# mark3.net
KiCad netlist of a schematic drawn in Altium Designer
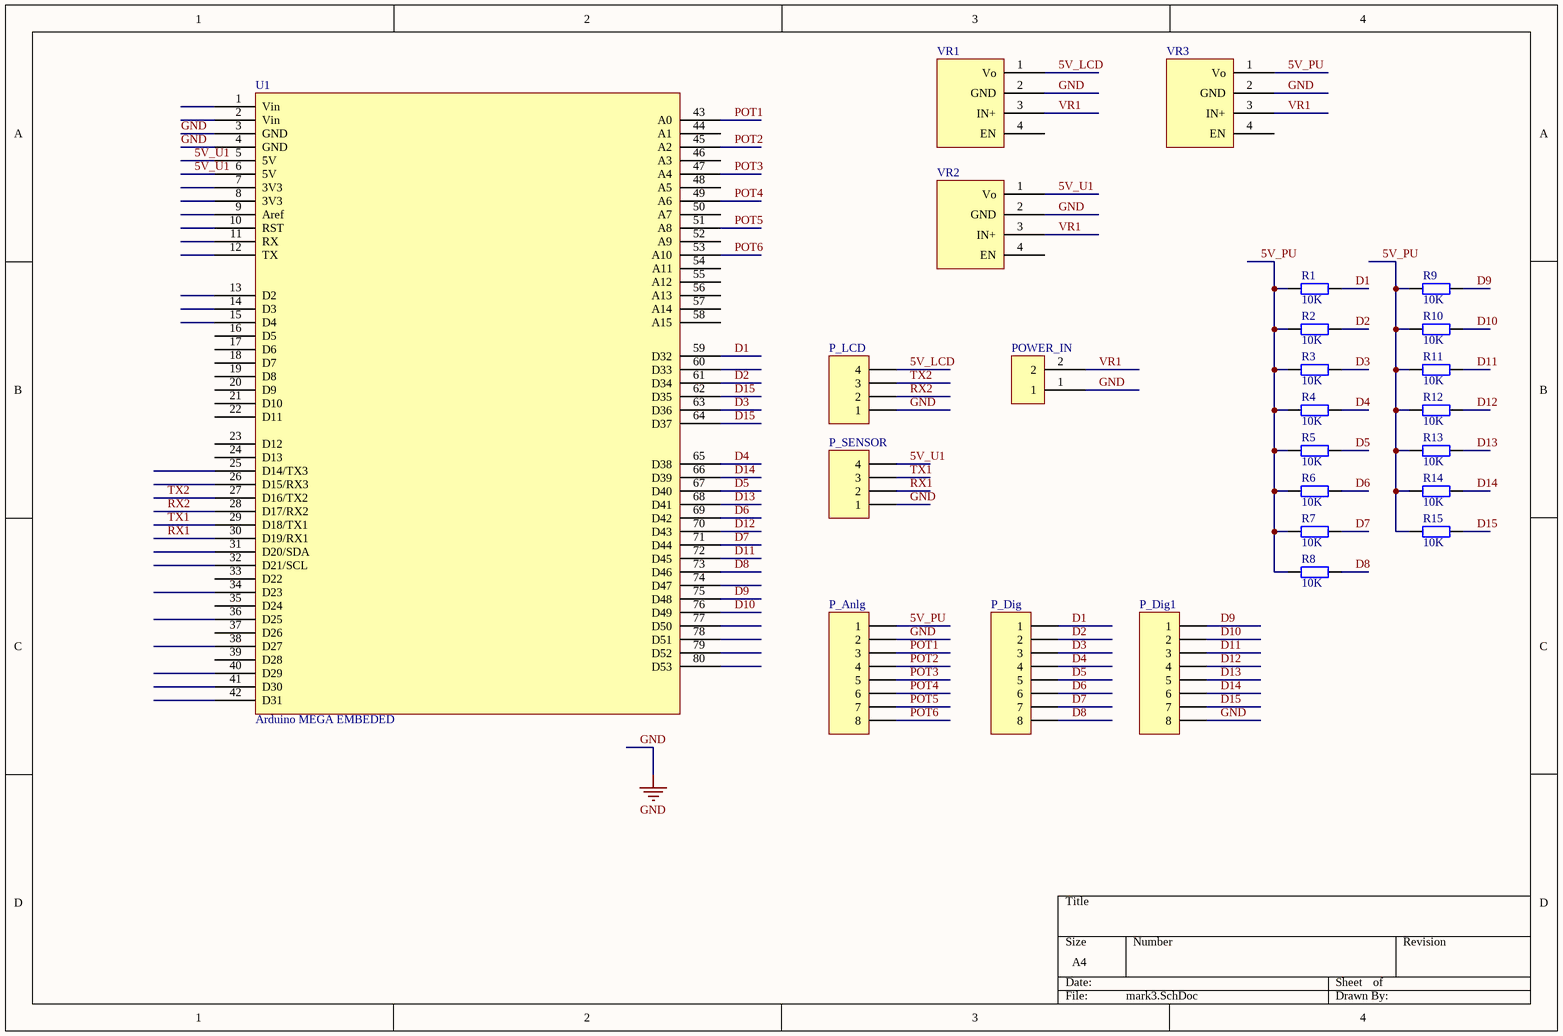
[diagram p0: mark3.SchDoc]

(export (version "E")
  (design (tool "Eeschema 10.0.6"))
  (components
    (comp (ref "POWER_IN")
      (value "Term_2Pin_Green")
      (footprint "TERM_2P_GREEN")
      (libsource (lib "arduino") (part "Term_2Pin_Blck"))
    )
    (comp (ref "P_Anlg")
      (value "Header 8")
      (footprint "TERM_8P_GREEN")
      (description "Header, 8-Pin")
      (fields (field (name "PUBLISHER") "Altium Limited"))
      (libsource (lib "Miscellaneous Connectors") (part "Header 8"))
    )
    (comp (ref "P_Dig")
      (value "Header 8")
      (footprint "TERM_8P_GREEN")
      (description "Header, 8-Pin")
      (fields (field (name "PUBLISHER") "Altium Limited"))
      (libsource (lib "Miscellaneous Connectors") (part "Header 8"))
    )
    (comp (ref "P_Dig1")
      (value "Header 8")
      (footprint "TERM_8P_GREEN")
      (description "Header, 8-Pin")
      (fields (field (name "PUBLISHER") "Altium Limited"))
      (libsource (lib "Miscellaneous Connectors") (part "Header 8"))
    )
    (comp (ref "P_LCD")
      (value "MHDR1X4")
      (footprint "TERM_4P_GREEN")
      (description "Header, 4-Pin")
      (fields (field (name "PUBLISHER") "Altium Limited"))
      (libsource (lib "Miscellaneous Connectors") (part "MHDR1X4"))
    )
    (comp (ref "P_SENSOR")
      (value "MHDR1X4")
      (footprint "TERM_4P_GREEN")
      (description "Header, 4-Pin")
      (fields (field (name "PUBLISHER") "Altium Limited"))
      (libsource (lib "Miscellaneous Connectors") (part "MHDR1X4"))
    )
    (comp (ref "R1")
      (value "10K")
      (footprint "AXIAL-0.4")
      (description "Resistor")
      (fields (field (name "Comment") "Res2") (field (name "PUBLISHER") "Altium Limited"))
      (libsource (lib "Miscellaneous Devices") (part "Res2"))
    )
    (comp (ref "R2")
      (value "10K")
      (footprint "AXIAL-0.4")
      (description "Resistor")
      (fields (field (name "Comment") "Res2") (field (name "PUBLISHER") "Altium Limited"))
      (libsource (lib "Miscellaneous Devices") (part "Res2"))
    )
    (comp (ref "R3")
      (value "10K")
      (footprint "AXIAL-0.4")
      (description "Resistor")
      (fields (field (name "Comment") "Res2") (field (name "PUBLISHER") "Altium Limited"))
      (libsource (lib "Miscellaneous Devices") (part "Res2"))
    )
    (comp (ref "R4")
      (value "10K")
      (footprint "AXIAL-0.4")
      (description "Resistor")
      (fields (field (name "Comment") "Res2") (field (name "PUBLISHER") "Altium Limited"))
      (libsource (lib "Miscellaneous Devices") (part "Res2"))
    )
    (comp (ref "R5")
      (value "10K")
      (footprint "AXIAL-0.4")
      (description "Resistor")
      (fields (field (name "Comment") "Res2") (field (name "PUBLISHER") "Altium Limited"))
      (libsource (lib "Miscellaneous Devices") (part "Res2"))
    )
    (comp (ref "R6")
      (value "10K")
      (footprint "AXIAL-0.4")
      (description "Resistor")
      (fields (field (name "Comment") "Res2") (field (name "PUBLISHER") "Altium Limited"))
      (libsource (lib "Miscellaneous Devices") (part "Res2"))
    )
    (comp (ref "R7")
      (value "10K")
      (footprint "AXIAL-0.4")
      (description "Resistor")
      (fields (field (name "Comment") "Res2") (field (name "PUBLISHER") "Altium Limited"))
      (libsource (lib "Miscellaneous Devices") (part "Res2"))
    )
    (comp (ref "R8")
      (value "10K")
      (footprint "AXIAL-0.4")
      (description "Resistor")
      (fields (field (name "Comment") "Res2") (field (name "PUBLISHER") "Altium Limited"))
      (libsource (lib "Miscellaneous Devices") (part "Res2"))
    )
    (comp (ref "R9")
      (value "10K")
      (footprint "AXIAL-0.4")
      (description "Resistor")
      (fields (field (name "Comment") "Res2") (field (name "PUBLISHER") "Altium Limited"))
      (libsource (lib "Miscellaneous Devices") (part "Res2"))
    )
    (comp (ref "R10")
      (value "10K")
      (footprint "AXIAL-0.4")
      (description "Resistor")
      (fields (field (name "Comment") "Res2") (field (name "PUBLISHER") "Altium Limited"))
      (libsource (lib "Miscellaneous Devices") (part "Res2"))
    )
    (comp (ref "R11")
      (value "10K")
      (footprint "AXIAL-0.4")
      (description "Resistor")
      (fields (field (name "Comment") "Res2") (field (name "PUBLISHER") "Altium Limited"))
      (libsource (lib "Miscellaneous Devices") (part "Res2"))
    )
    (comp (ref "R12")
      (value "10K")
      (footprint "AXIAL-0.4")
      (description "Resistor")
      (fields (field (name "Comment") "Res2") (field (name "PUBLISHER") "Altium Limited"))
      (libsource (lib "Miscellaneous Devices") (part "Res2"))
    )
    (comp (ref "R13")
      (value "10K")
      (footprint "AXIAL-0.4")
      (description "Resistor")
      (fields (field (name "Comment") "Res2") (field (name "PUBLISHER") "Altium Limited"))
      (libsource (lib "Miscellaneous Devices") (part "Res2"))
    )
    (comp (ref "R14")
      (value "10K")
      (footprint "AXIAL-0.4")
      (description "Resistor")
      (fields (field (name "Comment") "Res2") (field (name "PUBLISHER") "Altium Limited"))
      (libsource (lib "Miscellaneous Devices") (part "Res2"))
    )
    (comp (ref "R15")
      (value "10K")
      (footprint "AXIAL-0.4")
      (description "Resistor")
      (fields (field (name "Comment") "Res2") (field (name "PUBLISHER") "Altium Limited"))
      (libsource (lib "Miscellaneous Devices") (part "Res2"))
    )
    (comp (ref "U1")
      (value "Arduino MEGA EMBEDED")
      (footprint "ARDUINOMEGA")
      (libsource (lib "ArduinoShield") (part "Arduino MEGA EMBEDED"))
    )
    (comp (ref "VR1")
      (value "MODUL_LM2596_mini")
      (footprint "MODUL_LM2596_mini")
      (libsource (lib "ArduinoShield") (part "MODUL_LM2596_mini"))
    )
    (comp (ref "VR2")
      (value "MODUL_LM2596_mini")
      (footprint "MODUL_LM2596_mini")
      (libsource (lib "ArduinoShield") (part "MODUL_LM2596_mini"))
    )
    (comp (ref "VR3")
      (value "MODUL_LM2596_mini")
      (footprint "MODUL_LM2596_mini")
      (libsource (lib "ArduinoShield") (part "MODUL_LM2596_mini"))
    )
  )
  (nets
    (net (code "1") (name "/5V_LCD") (class "Default")
      (node (ref "P_LCD") (pin "4") (pinfunction "4_4") (pintype "passive"))
      (node (ref "VR1") (pin "1") (pinfunction "Vo_1") (pintype "passive"))
    )
    (net (code "2") (name "/5V_PU") (class "Default")
      (node (ref "P_Anlg") (pin "1") (pinfunction "1_1") (pintype "passive"))
      (node (ref "R1") (pin "2") (pinfunction "2_2") (pintype "passive"))
      (node (ref "R10") (pin "2") (pinfunction "2_2") (pintype "passive"))
      (node (ref "R11") (pin "2") (pinfunction "2_2") (pintype "passive"))
      (node (ref "R12") (pin "2") (pinfunction "2_2") (pintype "passive"))
      (node (ref "R13") (pin "2") (pinfunction "2_2") (pintype "passive"))
      (node (ref "R14") (pin "2") (pinfunction "2_2") (pintype "passive"))
      (node (ref "R15") (pin "2") (pinfunction "2_2") (pintype "passive"))
      (node (ref "R2") (pin "2") (pinfunction "2_2") (pintype "passive"))
      (node (ref "R3") (pin "2") (pinfunction "2_2") (pintype "passive"))
      (node (ref "R4") (pin "2") (pinfunction "2_2") (pintype "passive"))
      (node (ref "R5") (pin "2") (pinfunction "2_2") (pintype "passive"))
      (node (ref "R6") (pin "2") (pinfunction "2_2") (pintype "passive"))
      (node (ref "R7") (pin "2") (pinfunction "2_2") (pintype "passive"))
      (node (ref "R8") (pin "2") (pinfunction "2_2") (pintype "passive"))
      (node (ref "R9") (pin "2") (pinfunction "2_2") (pintype "passive"))
      (node (ref "VR3") (pin "1") (pinfunction "Vo_1") (pintype "passive"))
    )
    (net (code "3") (name "/5V_U1") (class "Default")
      (node (ref "P_SENSOR") (pin "4") (pinfunction "4_4") (pintype "passive"))
      (node (ref "U1") (pin "5") (pinfunction "5V_5") (pintype "passive"))
      (node (ref "U1") (pin "6") (pinfunction "5V_6") (pintype "passive"))
      (node (ref "VR2") (pin "1") (pinfunction "Vo_1") (pintype "passive"))
    )
    (net (code "4") (name "/D1") (class "Default")
      (node (ref "P_Dig") (pin "1") (pinfunction "1_1") (pintype "passive"))
      (node (ref "R1") (pin "1") (pinfunction "1_1") (pintype "passive"))
      (node (ref "U1") (pin "59") (pinfunction "D32_59") (pintype "passive"))
    )
    (net (code "5") (name "/D2") (class "Default")
      (node (ref "P_Dig") (pin "2") (pinfunction "2_2") (pintype "passive"))
      (node (ref "R2") (pin "1") (pinfunction "1_1") (pintype "passive"))
      (node (ref "U1") (pin "61") (pinfunction "D34_61") (pintype "passive"))
    )
    (net (code "6") (name "/D3") (class "Default")
      (node (ref "P_Dig") (pin "3") (pinfunction "3_3") (pintype "passive"))
      (node (ref "R3") (pin "1") (pinfunction "1_1") (pintype "passive"))
      (node (ref "U1") (pin "63") (pinfunction "D36_63") (pintype "passive"))
    )
    (net (code "7") (name "/D4") (class "Default")
      (node (ref "P_Dig") (pin "4") (pinfunction "4_4") (pintype "passive"))
      (node (ref "R4") (pin "1") (pinfunction "1_1") (pintype "passive"))
      (node (ref "U1") (pin "65") (pinfunction "D38_65") (pintype "passive"))
    )
    (net (code "8") (name "/D5") (class "Default")
      (node (ref "P_Dig") (pin "5") (pinfunction "5_5") (pintype "passive"))
      (node (ref "R5") (pin "1") (pinfunction "1_1") (pintype "passive"))
      (node (ref "U1") (pin "67") (pinfunction "D40_67") (pintype "passive"))
    )
    (net (code "9") (name "/D6") (class "Default")
      (node (ref "P_Dig") (pin "6") (pinfunction "6_6") (pintype "passive"))
      (node (ref "R6") (pin "1") (pinfunction "1_1") (pintype "passive"))
      (node (ref "U1") (pin "69") (pinfunction "D42_69") (pintype "passive"))
    )
    (net (code "10") (name "/D7") (class "Default")
      (node (ref "P_Dig") (pin "7") (pinfunction "7_7") (pintype "passive"))
      (node (ref "R7") (pin "1") (pinfunction "1_1") (pintype "passive"))
      (node (ref "U1") (pin "71") (pinfunction "D44_71") (pintype "passive"))
    )
    (net (code "11") (name "/D8") (class "Default")
      (node (ref "P_Dig") (pin "8") (pinfunction "8_8") (pintype "passive"))
      (node (ref "R8") (pin "1") (pinfunction "1_1") (pintype "passive"))
      (node (ref "U1") (pin "73") (pinfunction "D46_73") (pintype "passive"))
    )
    (net (code "12") (name "/D9") (class "Default")
      (node (ref "P_Dig1") (pin "1") (pinfunction "1_1") (pintype "passive"))
      (node (ref "R9") (pin "1") (pinfunction "1_1") (pintype "passive"))
      (node (ref "U1") (pin "75") (pinfunction "D48_75") (pintype "passive"))
    )
    (net (code "13") (name "/D10") (class "Default")
      (node (ref "P_Dig1") (pin "2") (pinfunction "2_2") (pintype "passive"))
      (node (ref "R10") (pin "1") (pinfunction "1_1") (pintype "passive"))
      (node (ref "U1") (pin "76") (pinfunction "D49_76") (pintype "passive"))
    )
    (net (code "14") (name "/D11") (class "Default")
      (node (ref "P_Dig1") (pin "3") (pinfunction "3_3") (pintype "passive"))
      (node (ref "R11") (pin "1") (pinfunction "1_1") (pintype "passive"))
      (node (ref "U1") (pin "72") (pinfunction "D45_72") (pintype "passive"))
    )
    (net (code "15") (name "/D12") (class "Default")
      (node (ref "P_Dig1") (pin "4") (pinfunction "4_4") (pintype "passive"))
      (node (ref "R12") (pin "1") (pinfunction "1_1") (pintype "passive"))
      (node (ref "U1") (pin "70") (pinfunction "D43_70") (pintype "passive"))
    )
    (net (code "16") (name "/D13") (class "Default")
      (node (ref "P_Dig1") (pin "5") (pinfunction "5_5") (pintype "passive"))
      (node (ref "R13") (pin "1") (pinfunction "1_1") (pintype "passive"))
      (node (ref "U1") (pin "68") (pinfunction "D41_68") (pintype "passive"))
    )
    (net (code "17") (name "/D14") (class "Default")
      (node (ref "P_Dig1") (pin "6") (pinfunction "6_6") (pintype "passive"))
      (node (ref "R14") (pin "1") (pinfunction "1_1") (pintype "passive"))
      (node (ref "U1") (pin "66") (pinfunction "D39_66") (pintype "passive"))
    )
    (net (code "18") (name "/D15") (class "Default")
      (node (ref "P_Dig1") (pin "7") (pinfunction "7_7") (pintype "passive"))
      (node (ref "R15") (pin "1") (pinfunction "1_1") (pintype "passive"))
      (node (ref "U1") (pin "62") (pinfunction "D35_62") (pintype "passive"))
      (node (ref "U1") (pin "64") (pinfunction "D37_64") (pintype "passive"))
    )
    (net (code "19") (name "/POT1") (class "Default")
      (node (ref "P_Anlg") (pin "3") (pinfunction "3_3") (pintype "passive"))
      (node (ref "U1") (pin "43") (pinfunction "A0_43") (pintype "passive"))
    )
    (net (code "20") (name "/POT2") (class "Default")
      (node (ref "P_Anlg") (pin "4") (pinfunction "4_4") (pintype "passive"))
      (node (ref "U1") (pin "45") (pinfunction "A2_45") (pintype "passive"))
    )
    (net (code "21") (name "/POT3") (class "Default")
      (node (ref "P_Anlg") (pin "5") (pinfunction "5_5") (pintype "passive"))
      (node (ref "U1") (pin "47") (pinfunction "A4_47") (pintype "passive"))
    )
    (net (code "22") (name "/POT4") (class "Default")
      (node (ref "P_Anlg") (pin "6") (pinfunction "6_6") (pintype "passive"))
      (node (ref "U1") (pin "49") (pinfunction "A6_49") (pintype "passive"))
    )
    (net (code "23") (name "/POT5") (class "Default")
      (node (ref "P_Anlg") (pin "7") (pinfunction "7_7") (pintype "passive"))
      (node (ref "U1") (pin "51") (pinfunction "A8_51") (pintype "passive"))
    )
    (net (code "24") (name "/POT6") (class "Default")
      (node (ref "P_Anlg") (pin "8") (pinfunction "8_8") (pintype "passive"))
      (node (ref "U1") (pin "53") (pinfunction "A10_53") (pintype "passive"))
    )
    (net (code "25") (name "/RX1") (class "Default")
      (node (ref "P_SENSOR") (pin "2") (pinfunction "2_2") (pintype "passive"))
      (node (ref "U1") (pin "30") (pinfunction "D19/RX1_30") (pintype "passive"))
    )
    (net (code "26") (name "/RX2") (class "Default")
      (node (ref "P_LCD") (pin "2") (pinfunction "2_2") (pintype "passive"))
      (node (ref "U1") (pin "28") (pinfunction "D17/RX2_28") (pintype "passive"))
    )
    (net (code "27") (name "/TX1") (class "Default")
      (node (ref "P_SENSOR") (pin "3") (pinfunction "3_3") (pintype "passive"))
      (node (ref "U1") (pin "29") (pinfunction "D18/TX1_29") (pintype "passive"))
    )
    (net (code "28") (name "/TX2") (class "Default")
      (node (ref "P_LCD") (pin "3") (pinfunction "3_3") (pintype "passive"))
      (node (ref "U1") (pin "27") (pinfunction "D16/TX2_27") (pintype "passive"))
    )
    (net (code "29") (name "/VR1") (class "Default")
      (node (ref "POWER_IN") (pin "2") (pinfunction "2_2") (pintype "passive"))
      (node (ref "VR1") (pin "3") (pinfunction "IN+_3") (pintype "passive"))
      (node (ref "VR2") (pin "3") (pinfunction "IN+_3") (pintype "passive"))
      (node (ref "VR3") (pin "3") (pinfunction "IN+_3") (pintype "passive"))
    )
    (net (code "30") (name "GND") (class "Default")
      (node (ref "POWER_IN") (pin "1") (pinfunction "1_1") (pintype "passive"))
      (node (ref "P_Anlg") (pin "2") (pinfunction "2_2") (pintype "passive"))
      (node (ref "P_Dig1") (pin "8") (pinfunction "8_8") (pintype "passive"))
      (node (ref "P_LCD") (pin "1") (pinfunction "1_1") (pintype "passive"))
      (node (ref "P_SENSOR") (pin "1") (pinfunction "1_1") (pintype "passive"))
      (node (ref "U1") (pin "3") (pinfunction "GND_3") (pintype "passive"))
      (node (ref "U1") (pin "4") (pinfunction "GND_4") (pintype "passive"))
      (node (ref "VR1") (pin "2") (pinfunction "GND_2") (pintype "passive"))
      (node (ref "VR2") (pin "2") (pinfunction "GND_2") (pintype "passive"))
      (node (ref "VR3") (pin "2") (pinfunction "GND_2") (pintype "passive"))
    )
    (net (code "31") (name "unconnected-(U1-3V3-Pad7)") (class "Default")
      (node (ref "U1") (pin "7") (pinfunction "3V3_7") (pintype "passive"))
    )
    (net (code "32") (name "unconnected-(U1-3V3-Pad8)") (class "Default")
      (node (ref "U1") (pin "8") (pinfunction "3V3_8") (pintype "passive"))
    )
    (net (code "33") (name "unconnected-(U1-A1-Pad44)") (class "Default")
      (node (ref "U1") (pin "44") (pinfunction "A1_44") (pintype "passive"))
    )
    (net (code "34") (name "unconnected-(U1-A3-Pad46)") (class "Default")
      (node (ref "U1") (pin "46") (pinfunction "A3_46") (pintype "passive"))
    )
    (net (code "35") (name "unconnected-(U1-A5-Pad48)") (class "Default")
      (node (ref "U1") (pin "48") (pinfunction "A5_48") (pintype "passive"))
    )
    (net (code "36") (name "unconnected-(U1-A7-Pad50)") (class "Default")
      (node (ref "U1") (pin "50") (pinfunction "A7_50") (pintype "passive"))
    )
    (net (code "37") (name "unconnected-(U1-A9-Pad52)") (class "Default")
      (node (ref "U1") (pin "52") (pinfunction "A9_52") (pintype "passive"))
    )
    (net (code "38") (name "unconnected-(U1-A11-Pad54)") (class "Default")
      (node (ref "U1") (pin "54") (pinfunction "A11_54") (pintype "passive"))
    )
    (net (code "39") (name "unconnected-(U1-A12-Pad55)") (class "Default")
      (node (ref "U1") (pin "55") (pinfunction "A12_55") (pintype "passive"))
    )
    (net (code "40") (name "unconnected-(U1-A13-Pad56)") (class "Default")
      (node (ref "U1") (pin "56") (pinfunction "A13_56") (pintype "passive"))
    )
    (net (code "41") (name "unconnected-(U1-A14-Pad57)") (class "Default")
      (node (ref "U1") (pin "57") (pinfunction "A14_57") (pintype "passive"))
    )
    (net (code "42") (name "unconnected-(U1-A15-Pad58)") (class "Default")
      (node (ref "U1") (pin "58") (pinfunction "A15_58") (pintype "passive"))
    )
    (net (code "43") (name "unconnected-(U1-Aref-Pad9)") (class "Default")
      (node (ref "U1") (pin "9") (pinfunction "Aref_9") (pintype "passive"))
    )
    (net (code "44") (name "unconnected-(U1-D2-Pad13)") (class "Default")
      (node (ref "U1") (pin "13") (pinfunction "D2_13") (pintype "passive"))
    )
    (net (code "45") (name "unconnected-(U1-D3-Pad14)") (class "Default")
      (node (ref "U1") (pin "14") (pinfunction "D3_14") (pintype "passive"))
    )
    (net (code "46") (name "unconnected-(U1-D4-Pad15)") (class "Default")
      (node (ref "U1") (pin "15") (pinfunction "D4_15") (pintype "passive"))
    )
    (net (code "47") (name "unconnected-(U1-D5-Pad16)") (class "Default")
      (node (ref "U1") (pin "16") (pinfunction "D5_16") (pintype "passive"))
    )
    (net (code "48") (name "unconnected-(U1-D6-Pad17)") (class "Default")
      (node (ref "U1") (pin "17") (pinfunction "D6_17") (pintype "passive"))
    )
    (net (code "49") (name "unconnected-(U1-D7-Pad18)") (class "Default")
      (node (ref "U1") (pin "18") (pinfunction "D7_18") (pintype "passive"))
    )
    (net (code "50") (name "unconnected-(U1-D8-Pad19)") (class "Default")
      (node (ref "U1") (pin "19") (pinfunction "D8_19") (pintype "passive"))
    )
    (net (code "51") (name "unconnected-(U1-D9-Pad20)") (class "Default")
      (node (ref "U1") (pin "20") (pinfunction "D9_20") (pintype "passive"))
    )
    (net (code "52") (name "unconnected-(U1-D10-Pad21)") (class "Default")
      (node (ref "U1") (pin "21") (pinfunction "D10_21") (pintype "passive"))
    )
    (net (code "53") (name "unconnected-(U1-D11-Pad22)") (class "Default")
      (node (ref "U1") (pin "22") (pinfunction "D11_22") (pintype "passive"))
    )
    (net (code "54") (name "unconnected-(U1-D12-Pad23)") (class "Default")
      (node (ref "U1") (pin "23") (pinfunction "D12_23") (pintype "passive"))
    )
    (net (code "55") (name "unconnected-(U1-D13-Pad24)") (class "Default")
      (node (ref "U1") (pin "24") (pinfunction "D13_24") (pintype "passive"))
    )
    (net (code "56") (name "unconnected-(U1-D14{slash}TX3-Pad25)") (class "Default")
      (node (ref "U1") (pin "25") (pinfunction "D14/TX3_25") (pintype "passive"))
    )
    (net (code "57") (name "unconnected-(U1-D15{slash}RX3-Pad26)") (class "Default")
      (node (ref "U1") (pin "26") (pinfunction "D15/RX3_26") (pintype "passive"))
    )
    (net (code "58") (name "unconnected-(U1-D20{slash}SDA-Pad31)") (class "Default")
      (node (ref "U1") (pin "31") (pinfunction "D20/SDA_31") (pintype "passive"))
    )
    (net (code "59") (name "unconnected-(U1-D21{slash}SCL-Pad32)") (class "Default")
      (node (ref "U1") (pin "32") (pinfunction "D21/SCL_32") (pintype "passive"))
    )
    (net (code "60") (name "unconnected-(U1-D22-Pad33)") (class "Default")
      (node (ref "U1") (pin "33") (pinfunction "D22_33") (pintype "passive"))
    )
    (net (code "61") (name "unconnected-(U1-D23-Pad34)") (class "Default")
      (node (ref "U1") (pin "34") (pinfunction "D23_34") (pintype "passive"))
    )
    (net (code "62") (name "unconnected-(U1-D24-Pad35)") (class "Default")
      (node (ref "U1") (pin "35") (pinfunction "D24_35") (pintype "passive"))
    )
    (net (code "63") (name "unconnected-(U1-D25-Pad36)") (class "Default")
      (node (ref "U1") (pin "36") (pinfunction "D25_36") (pintype "passive"))
    )
    (net (code "64") (name "unconnected-(U1-D26-Pad37)") (class "Default")
      (node (ref "U1") (pin "37") (pinfunction "D26_37") (pintype "passive"))
    )
    (net (code "65") (name "unconnected-(U1-D27-Pad38)") (class "Default")
      (node (ref "U1") (pin "38") (pinfunction "D27_38") (pintype "passive"))
    )
    (net (code "66") (name "unconnected-(U1-D28-Pad39)") (class "Default")
      (node (ref "U1") (pin "39") (pinfunction "D28_39") (pintype "passive"))
    )
    (net (code "67") (name "unconnected-(U1-D29-Pad40)") (class "Default")
      (node (ref "U1") (pin "40") (pinfunction "D29_40") (pintype "passive"))
    )
    (net (code "68") (name "unconnected-(U1-D30-Pad41)") (class "Default")
      (node (ref "U1") (pin "41") (pinfunction "D30_41") (pintype "passive"))
    )
    (net (code "69") (name "unconnected-(U1-D31-Pad42)") (class "Default")
      (node (ref "U1") (pin "42") (pinfunction "D31_42") (pintype "passive"))
    )
    (net (code "70") (name "unconnected-(U1-D33-Pad60)") (class "Default")
      (node (ref "U1") (pin "60") (pinfunction "D33_60") (pintype "passive"))
    )
    (net (code "71") (name "unconnected-(U1-D47-Pad74)") (class "Default")
      (node (ref "U1") (pin "74") (pinfunction "D47_74") (pintype "passive"))
    )
    (net (code "72") (name "unconnected-(U1-D50-Pad77)") (class "Default")
      (node (ref "U1") (pin "77") (pinfunction "D50_77") (pintype "passive"))
    )
    (net (code "73") (name "unconnected-(U1-D51-Pad78)") (class "Default")
      (node (ref "U1") (pin "78") (pinfunction "D51_78") (pintype "passive"))
    )
    (net (code "74") (name "unconnected-(U1-D52-Pad79)") (class "Default")
      (node (ref "U1") (pin "79") (pinfunction "D52_79") (pintype "passive"))
    )
    (net (code "75") (name "unconnected-(U1-D53-Pad80)") (class "Default")
      (node (ref "U1") (pin "80") (pinfunction "D53_80") (pintype "passive"))
    )
    (net (code "76") (name "unconnected-(U1-RST-Pad10)") (class "Default")
      (node (ref "U1") (pin "10") (pinfunction "RST_10") (pintype "passive"))
    )
    (net (code "77") (name "unconnected-(U1-RX-Pad11)") (class "Default")
      (node (ref "U1") (pin "11") (pinfunction "RX_11") (pintype "passive"))
    )
    (net (code "78") (name "unconnected-(U1-TX-Pad12)") (class "Default")
      (node (ref "U1") (pin "12") (pinfunction "TX_12") (pintype "passive"))
    )
    (net (code "79") (name "unconnected-(U1-Vin-Pad1)") (class "Default")
      (node (ref "U1") (pin "1") (pinfunction "Vin_1") (pintype "passive"))
    )
    (net (code "80") (name "unconnected-(U1-Vin-Pad2)") (class "Default")
      (node (ref "U1") (pin "2") (pinfunction "Vin_2") (pintype "passive"))
    )
    (net (code "81") (name "unconnected-(VR1-EN-Pad4)") (class "Default")
      (node (ref "VR1") (pin "4") (pinfunction "EN_4") (pintype "passive"))
    )
    (net (code "82") (name "unconnected-(VR2-EN-Pad4)") (class "Default")
      (node (ref "VR2") (pin "4") (pinfunction "EN_4") (pintype "passive"))
    )
    (net (code "83") (name "unconnected-(VR3-EN-Pad4)") (class "Default")
      (node (ref "VR3") (pin "4") (pinfunction "EN_4") (pintype "passive"))
    )
  )
)
